# My_Smart_Home_Rev2.net
KiCad netlist of a schematic drawn in EAGLE
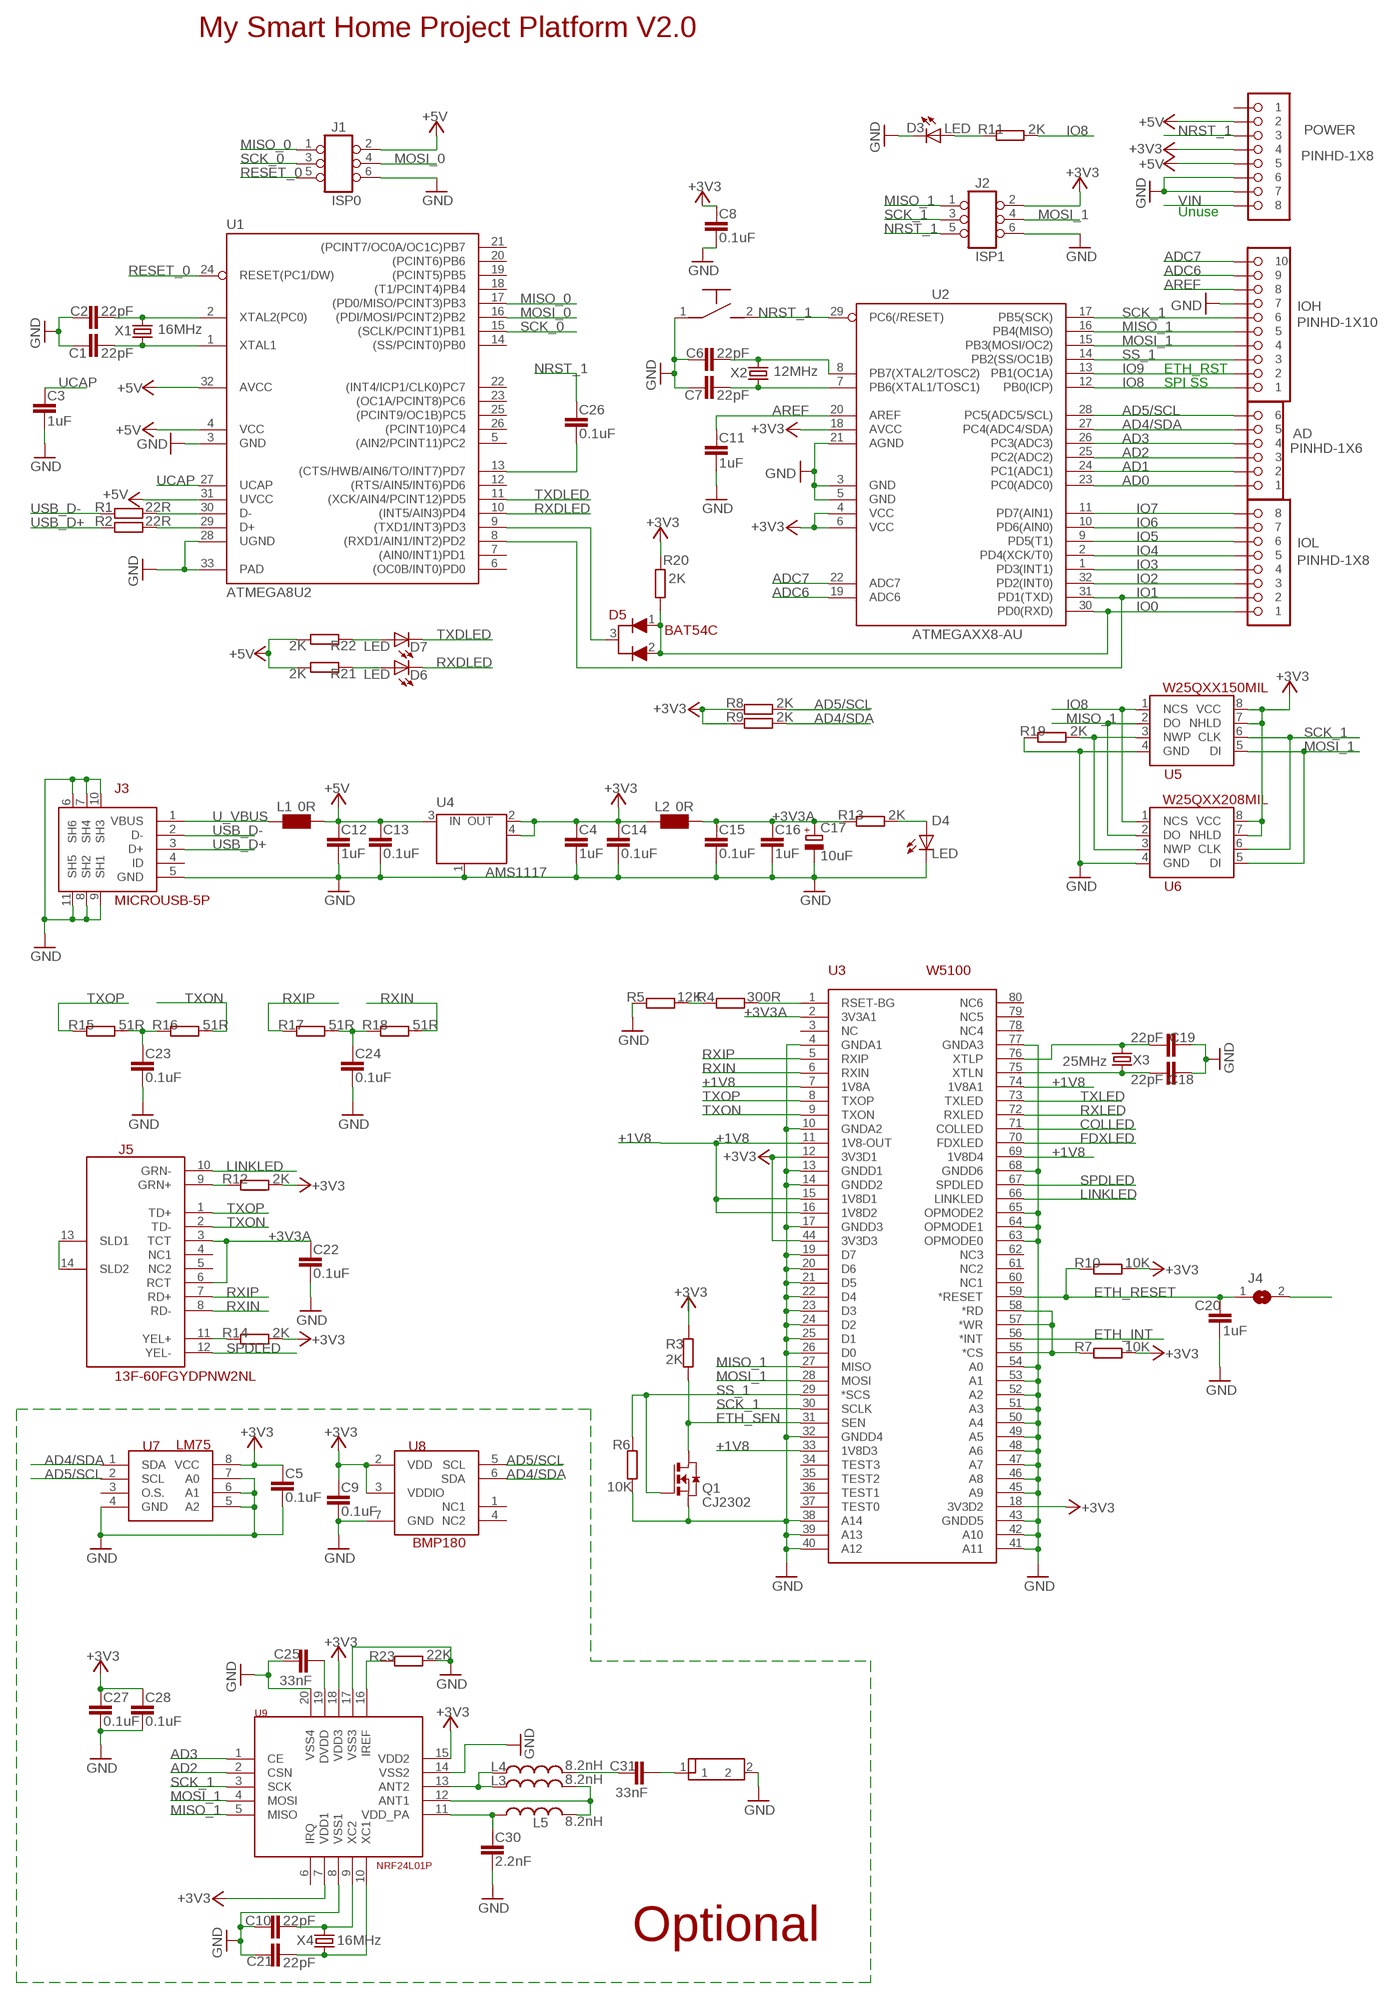
[diagram p0: schematic, sheet 1]

(export (version "E")
  (design (tool "Eeschema 10.0.6"))
  (components
    (comp (ref "AD")
      (value "PINHD-1X6")
      (footprint "eagle-import:1X06")
      (libsource (lib "eagle-import") (part "PINHD-1X6"))
    )
    (comp (ref "ANT1")
      (value "2.4G_ANT1")
      (footprint "eagle-import:2.4G_PCB_ANT")
      (libsource (lib "eagle-import") (part "2.4G_ANT1"))
    )
    (comp (ref "C1")
      (value "22pF")
      (footprint "eagle-import:C0603")
      (libsource (lib "eagle-import") (part "C-NP"))
    )
    (comp (ref "C2")
      (value "22pF")
      (footprint "eagle-import:C0603")
      (libsource (lib "eagle-import") (part "C-NP"))
    )
    (comp (ref "C3")
      (value "1uF")
      (footprint "eagle-import:C0603")
      (libsource (lib "eagle-import") (part "C-NP"))
    )
    (comp (ref "C4")
      (value "1uF")
      (footprint "eagle-import:C0603")
      (libsource (lib "eagle-import") (part "C-NP"))
    )
    (comp (ref "C5")
      (value "0.1uF")
      (footprint "eagle-import:C0603")
      (libsource (lib "eagle-import") (part "C-NP"))
    )
    (comp (ref "C6")
      (value "22pF")
      (footprint "eagle-import:C0603")
      (libsource (lib "eagle-import") (part "C-NP"))
    )
    (comp (ref "C7")
      (value "22pF")
      (footprint "eagle-import:C0603")
      (libsource (lib "eagle-import") (part "C-NP"))
    )
    (comp (ref "C8")
      (value "0.1uF")
      (footprint "eagle-import:C0603")
      (libsource (lib "eagle-import") (part "C-NP"))
    )
    (comp (ref "C9")
      (value "0.1uF")
      (footprint "eagle-import:C0603")
      (libsource (lib "eagle-import") (part "C-NP"))
    )
    (comp (ref "C10")
      (value "22pF")
      (footprint "eagle-import:C0603")
      (libsource (lib "eagle-import") (part "C-NP"))
    )
    (comp (ref "C11")
      (value "1uF")
      (footprint "eagle-import:C0603")
      (libsource (lib "eagle-import") (part "C-NP"))
    )
    (comp (ref "C12")
      (value "1uF")
      (footprint "eagle-import:C0603")
      (libsource (lib "eagle-import") (part "C-NP"))
    )
    (comp (ref "C13")
      (value "0.1uF")
      (footprint "eagle-import:C0603")
      (libsource (lib "eagle-import") (part "C-NP"))
    )
    (comp (ref "C14")
      (value "0.1uF")
      (footprint "eagle-import:C0603")
      (libsource (lib "eagle-import") (part "C-NP"))
    )
    (comp (ref "C15")
      (value "0.1uF")
      (footprint "eagle-import:C0603")
      (libsource (lib "eagle-import") (part "C-NP"))
    )
    (comp (ref "C16")
      (value "1uF")
      (footprint "eagle-import:C0603")
      (libsource (lib "eagle-import") (part "C-NP"))
    )
    (comp (ref "C17")
      (value "10uF")
      (footprint "eagle-import:C0805")
      (libsource (lib "eagle-import") (part "C-POL"))
    )
    (comp (ref "C18")
      (value "22pF")
      (footprint "eagle-import:C0603")
      (libsource (lib "eagle-import") (part "C-NP"))
    )
    (comp (ref "C19")
      (value "22pF")
      (footprint "eagle-import:C0603")
      (libsource (lib "eagle-import") (part "C-NP"))
    )
    (comp (ref "C20")
      (value "1uF")
      (footprint "eagle-import:C0603")
      (libsource (lib "eagle-import") (part "C-NP"))
    )
    (comp (ref "C21")
      (value "22pF")
      (footprint "eagle-import:C0603")
      (libsource (lib "eagle-import") (part "C-NP"))
    )
    (comp (ref "C22")
      (value "0.1uF")
      (footprint "eagle-import:C0603")
      (libsource (lib "eagle-import") (part "C-NP"))
    )
    (comp (ref "C23")
      (value "0.1uF")
      (footprint "eagle-import:C0603")
      (libsource (lib "eagle-import") (part "C-NP"))
    )
    (comp (ref "C24")
      (value "0.1uF")
      (footprint "eagle-import:C0603")
      (libsource (lib "eagle-import") (part "C-NP"))
    )
    (comp (ref "C25")
      (value "33nF")
      (footprint "eagle-import:C0603")
      (libsource (lib "eagle-import") (part "C-NP"))
    )
    (comp (ref "C26")
      (value "0.1uF")
      (footprint "eagle-import:C0603")
      (libsource (lib "eagle-import") (part "C-NP"))
    )
    (comp (ref "C27")
      (value "0.1uF")
      (footprint "eagle-import:C0603")
      (libsource (lib "eagle-import") (part "C-NP"))
    )
    (comp (ref "C28")
      (value "0.1uF")
      (footprint "eagle-import:C0603")
      (libsource (lib "eagle-import") (part "C-NP"))
    )
    (comp (ref "C30")
      (value "2.2nF")
      (footprint "eagle-import:C0603")
      (libsource (lib "eagle-import") (part "C-NP"))
    )
    (comp (ref "C31")
      (value "33nF")
      (footprint "eagle-import:C0603")
      (libsource (lib "eagle-import") (part "C-NP"))
    )
    (comp (ref "D3")
      (value "LED")
      (footprint "eagle-import:LED0805")
      (libsource (lib "eagle-import") (part "LED"))
    )
    (comp (ref "D4")
      (value "LED")
      (footprint "eagle-import:LED0805")
      (libsource (lib "eagle-import") (part "LED"))
    )
    (comp (ref "D5")
      (value "BAT54C")
      (footprint "eagle-import:SOT23")
      (libsource (lib "eagle-import") (part "BAT54C"))
    )
    (comp (ref "D6")
      (value "LED")
      (footprint "eagle-import:LED0805")
      (libsource (lib "eagle-import") (part "LED"))
    )
    (comp (ref "D7")
      (value "LED")
      (footprint "eagle-import:LED0805")
      (libsource (lib "eagle-import") (part "LED"))
    )
    (comp (ref "IOH")
      (value "PINHD-1X10")
      (footprint "eagle-import:1X10")
      (libsource (lib "eagle-import") (part "PINHD-1X10"))
    )
    (comp (ref "IOL")
      (value "PINHD-1X8")
      (footprint "eagle-import:1X08")
      (libsource (lib "eagle-import") (part "PINHD-1X8"))
    )
    (comp (ref "J1")
      (value "ISP0")
      (footprint "eagle-import:2X03")
      (libsource (lib "eagle-import") (part "PINHD-2X3"))
    )
    (comp (ref "J2")
      (value "ISP1")
      (footprint "eagle-import:2X03")
      (libsource (lib "eagle-import") (part "PINHD-2X3"))
    )
    (comp (ref "J3")
      (value "MICROUSB-5P")
      (footprint "eagle-import:MICROUSB-5P-SMD")
      (libsource (lib "eagle-import") (part "MICROUSB-5P"))
    )
    (comp (ref "J4")
      (value "JUMPER")
      (footprint "eagle-import:SOLDER_JUMPER")
      (libsource (lib "eagle-import") (part "JUMPER"))
    )
    (comp (ref "J5")
      (value "13F-60FGYDPNW2NL")
      (footprint "eagle-import:13F-60FGYDPNW2NL")
      (libsource (lib "eagle-import") (part "13F-60FGYDPNW2NL"))
    )
    (comp (ref "L1")
      (value "0R")
      (footprint "eagle-import:R0603")
      (libsource (lib "eagle-import") (part "L_M"))
    )
    (comp (ref "L2")
      (value "0R")
      (footprint "eagle-import:R0603")
      (libsource (lib "eagle-import") (part "L_M"))
    )
    (comp (ref "L3")
      (value "8.2nH")
      (footprint "eagle-import:R0603")
      (libsource (lib "eagle-import") (part "L"))
    )
    (comp (ref "L4")
      (value "8.2nH")
      (footprint "eagle-import:R0603")
      (libsource (lib "eagle-import") (part "L"))
    )
    (comp (ref "L5")
      (value "8.2nH")
      (footprint "eagle-import:R0603")
      (libsource (lib "eagle-import") (part "L"))
    )
    (comp (ref "POWER")
      (value "PINHD-1X8")
      (footprint "eagle-import:1X08")
      (libsource (lib "eagle-import") (part "PINHD-1X8"))
    )
    (comp (ref "Q1")
      (value "CJ2302")
      (footprint "eagle-import:SOT23")
      (libsource (lib "eagle-import") (part "NMOS-SOT23"))
    )
    (comp (ref "R1")
      (value "22R")
      (footprint "eagle-import:R0603")
      (libsource (lib "eagle-import") (part "RES"))
    )
    (comp (ref "R2")
      (value "22R")
      (footprint "eagle-import:R0603")
      (libsource (lib "eagle-import") (part "RES"))
    )
    (comp (ref "R3")
      (value "2K")
      (footprint "eagle-import:R0603")
      (libsource (lib "eagle-import") (part "RES"))
    )
    (comp (ref "R4")
      (value "300R")
      (footprint "eagle-import:R0603")
      (libsource (lib "eagle-import") (part "RES"))
    )
    (comp (ref "R5")
      (value "12K")
      (footprint "eagle-import:R0603")
      (libsource (lib "eagle-import") (part "RES"))
    )
    (comp (ref "R6")
      (value "10K")
      (footprint "eagle-import:R0603")
      (libsource (lib "eagle-import") (part "RES"))
    )
    (comp (ref "R7")
      (value "10K")
      (footprint "eagle-import:R0603")
      (libsource (lib "eagle-import") (part "RES"))
    )
    (comp (ref "R8")
      (value "2K")
      (footprint "eagle-import:R0603")
      (libsource (lib "eagle-import") (part "RES"))
    )
    (comp (ref "R9")
      (value "2K")
      (footprint "eagle-import:R0603")
      (libsource (lib "eagle-import") (part "RES"))
    )
    (comp (ref "R10")
      (value "10K")
      (footprint "eagle-import:R0603")
      (libsource (lib "eagle-import") (part "RES"))
    )
    (comp (ref "R11")
      (value "2K")
      (footprint "eagle-import:R0603")
      (libsource (lib "eagle-import") (part "RES"))
    )
    (comp (ref "R12")
      (value "2K")
      (footprint "eagle-import:R0603")
      (libsource (lib "eagle-import") (part "RES"))
    )
    (comp (ref "R13")
      (value "2K")
      (footprint "eagle-import:R0603")
      (libsource (lib "eagle-import") (part "RES"))
    )
    (comp (ref "R14")
      (value "2K")
      (footprint "eagle-import:R0603")
      (libsource (lib "eagle-import") (part "RES"))
    )
    (comp (ref "R15")
      (value "51R")
      (footprint "eagle-import:R0603")
      (libsource (lib "eagle-import") (part "RES"))
    )
    (comp (ref "R16")
      (value "51R")
      (footprint "eagle-import:R0603")
      (libsource (lib "eagle-import") (part "RES"))
    )
    (comp (ref "R17")
      (value "51R")
      (footprint "eagle-import:R0603")
      (libsource (lib "eagle-import") (part "RES"))
    )
    (comp (ref "R18")
      (value "51R")
      (footprint "eagle-import:R0603")
      (libsource (lib "eagle-import") (part "RES"))
    )
    (comp (ref "R19")
      (value "2K")
      (footprint "eagle-import:R0603")
      (libsource (lib "eagle-import") (part "RES"))
    )
    (comp (ref "R20")
      (value "2K")
      (footprint "eagle-import:R0603")
      (libsource (lib "eagle-import") (part "RES"))
    )
    (comp (ref "R21")
      (value "2K")
      (footprint "eagle-import:R0603")
      (libsource (lib "eagle-import") (part "RES"))
    )
    (comp (ref "R22")
      (value "2K")
      (footprint "eagle-import:R0603")
      (libsource (lib "eagle-import") (part "RES"))
    )
    (comp (ref "R23")
      (value "22K")
      (footprint "eagle-import:R0603")
      (libsource (lib "eagle-import") (part "RES"))
    )
    (comp (ref "SW2")
      (value "SW-2")
      (footprint "eagle-import:SW-2P-SMD")
      (libsource (lib "eagle-import") (part "SW-2"))
    )
    (comp (ref "U1")
      (value "ATMEGA8U2")
      (footprint "eagle-import:MLF32")
      (libsource (lib "eagle-import") (part "ATMEGA8U2"))
    )
    (comp (ref "U2")
      (value "ATMEGAXX8-AU")
      (footprint "eagle-import:TQFP32-08")
      (libsource (lib "eagle-import") (part "ATMEGAXX8-AU"))
    )
    (comp (ref "U3")
      (value "W5100")
      (footprint "eagle-import:SQFP-S-10X10-80")
      (libsource (lib "eagle-import") (part "W5100"))
    )
    (comp (ref "U4")
      (value "AMS1117")
      (footprint "eagle-import:SOT223")
      (libsource (lib "eagle-import") (part "AMS1117"))
    )
    (comp (ref "U5")
      (value "W25QXX150MIL")
      (footprint "eagle-import:8S1")
      (libsource (lib "eagle-import") (part "W25QXX150MIL"))
    )
    (comp (ref "U6")
      (value "W25QXX208MIL")
      (footprint "eagle-import:8S2")
      (libsource (lib "eagle-import") (part "W25QXX208MIL"))
    )
    (comp (ref "U7")
      (value "LM75")
      (footprint "eagle-import:8S1")
      (libsource (lib "eagle-import") (part "LM75"))
    )
    (comp (ref "U8")
      (value "BMP180")
      (footprint "eagle-import:LGA-7P")
      (libsource (lib "eagle-import") (part "BMP180"))
    )
    (comp (ref "U9")
      (value "NRF24L01P")
      (footprint "eagle-import:QFN20")
      (libsource (lib "eagle-import") (part "NRF24L01P"))
    )
    (comp (ref "X1")
      (value "16MHz")
      (footprint "eagle-import:HC49UP")
      (libsource (lib "eagle-import") (part "CRYSTAL"))
    )
    (comp (ref "X2")
      (value "12MHz")
      (footprint "eagle-import:HC49UP")
      (libsource (lib "eagle-import") (part "CRYSTAL"))
    )
    (comp (ref "X3")
      (value "25MHz")
      (footprint "eagle-import:HC49UP")
      (libsource (lib "eagle-import") (part "CRYSTAL"))
    )
    (comp (ref "X4")
      (value "16MHz")
      (footprint "eagle-import:HC49UP")
      (libsource (lib "eagle-import") (part "CRYSTAL"))
    )
  )
  (nets
    (net (code "1") (name "+3V3") (class "Default")
      (node (ref "C14") (pin "2") (pinfunction "2_2") (pintype "passive"))
      (node (ref "C27") (pin "2") (pinfunction "2_2") (pintype "passive"))
      (node (ref "C28") (pin "2") (pinfunction "2_2") (pintype "passive"))
      (node (ref "C4") (pin "2") (pinfunction "2_2") (pintype "passive"))
      (node (ref "C5") (pin "2") (pinfunction "2_2") (pintype "passive"))
      (node (ref "C8") (pin "2") (pinfunction "2_2") (pintype "passive"))
      (node (ref "C9") (pin "2") (pinfunction "2_2") (pintype "passive"))
      (node (ref "J2") (pin "2") (pinfunction "2_2") (pintype "passive"))
      (node (ref "L2") (pin "1") (pinfunction "1_1") (pintype "passive"))
      (node (ref "POWER") (pin "4") (pinfunction "4_4") (pintype "passive"))
      (node (ref "R10") (pin "2") (pinfunction "2_2") (pintype "passive"))
      (node (ref "R12") (pin "1") (pinfunction "1_1") (pintype "passive"))
      (node (ref "R14") (pin "1") (pinfunction "1_1") (pintype "passive"))
      (node (ref "R20") (pin "2") (pinfunction "2_2") (pintype "passive"))
      (node (ref "R3") (pin "2") (pinfunction "2_2") (pintype "passive"))
      (node (ref "R7") (pin "2") (pinfunction "2_2") (pintype "passive"))
      (node (ref "R8") (pin "2") (pinfunction "2_2") (pintype "passive"))
      (node (ref "R9") (pin "2") (pinfunction "2_2") (pintype "passive"))
      (node (ref "U2") (pin "18") (pinfunction "AVCC_18") (pintype "bidirectional"))
      (node (ref "U2") (pin "4") (pinfunction "VCC_4") (pintype "bidirectional"))
      (node (ref "U2") (pin "6") (pinfunction "VCC_6") (pintype "bidirectional"))
      (node (ref "U3") (pin "12") (pinfunction "3V3D1_12") (pintype "power_in"))
      (node (ref "U3") (pin "18") (pinfunction "3V3D2_18") (pintype "power_in"))
      (node (ref "U3") (pin "44") (pinfunction "3V3D3_44") (pintype "power_in"))
      (node (ref "U4") (pin "2") (pinfunction "OUT_2") (pintype "passive"))
      (node (ref "U4") (pin "4") (pinfunction "OUT_4") (pintype "passive"))
      (node (ref "U5") (pin "7") (pinfunction "NHLD_7") (pintype "bidirectional"))
      (node (ref "U5") (pin "8") (pinfunction "VCC_8") (pintype "bidirectional"))
      (node (ref "U6") (pin "7") (pinfunction "NHLD_7") (pintype "bidirectional"))
      (node (ref "U6") (pin "8") (pinfunction "VCC_8") (pintype "bidirectional"))
      (node (ref "U7") (pin "8") (pinfunction "VCC_8") (pintype "bidirectional"))
      (node (ref "U8") (pin "2") (pinfunction "VDD_2") (pintype "bidirectional"))
      (node (ref "U8") (pin "3") (pinfunction "VDDIO_3") (pintype "bidirectional"))
      (node (ref "U9") (pin "15") (pinfunction "VDD2_15") (pintype "bidirectional"))
      (node (ref "U9") (pin "18") (pinfunction "VDD3_18") (pintype "bidirectional"))
      (node (ref "U9") (pin "7") (pinfunction "VDD1_7") (pintype "bidirectional"))
    )
    (net (code "2") (name "+5V") (class "Default")
      (node (ref "C12") (pin "2") (pinfunction "2_2") (pintype "passive"))
      (node (ref "C13") (pin "2") (pinfunction "2_2") (pintype "passive"))
      (node (ref "J1") (pin "2") (pinfunction "2_2") (pintype "passive"))
      (node (ref "L1") (pin "2") (pinfunction "2_2") (pintype "passive"))
      (node (ref "POWER") (pin "2") (pinfunction "2_2") (pintype "passive"))
      (node (ref "POWER") (pin "5") (pinfunction "5_5") (pintype "passive"))
      (node (ref "R21") (pin "1") (pinfunction "1_1") (pintype "passive"))
      (node (ref "R22") (pin "1") (pinfunction "1_1") (pintype "passive"))
      (node (ref "U1") (pin "31") (pinfunction "UVCC_31") (pintype "power_in"))
      (node (ref "U1") (pin "32") (pinfunction "AVCC_32") (pintype "power_in"))
      (node (ref "U1") (pin "4") (pinfunction "VCC_4") (pintype "power_in"))
      (node (ref "U4") (pin "3") (pinfunction "IN_3") (pintype "input"))
    )
    (net (code "3") (name "/+1V8") (class "Default")
      (node (ref "U3") (pin "11") (pinfunction "1V8-OUT_11") (pintype "power_in"))
      (node (ref "U3") (pin "15") (pinfunction "1V8D1_15") (pintype "power_in"))
      (node (ref "U3") (pin "16") (pinfunction "1V8D2_16") (pintype "power_in"))
      (node (ref "U3") (pin "33") (pinfunction "1V8D3_33") (pintype "power_in"))
      (node (ref "U3") (pin "69") (pinfunction "1V8D4_69") (pintype "power_in"))
      (node (ref "U3") (pin "7") (pinfunction "1V8A_7") (pintype "power_in"))
      (node (ref "U3") (pin "74") (pinfunction "1V8A1_74") (pintype "power_in"))
    )
    (net (code "4") (name "/+3V3A") (class "Default")
      (node (ref "C15") (pin "2") (pinfunction "2_2") (pintype "passive"))
      (node (ref "C16") (pin "2") (pinfunction "2_2") (pintype "passive"))
      (node (ref "C17") (pin "1") (pinfunction "+_1") (pintype "passive"))
      (node (ref "C22") (pin "2") (pinfunction "2_2") (pintype "passive"))
      (node (ref "J5") (pin "3") (pinfunction "TCT_3") (pintype "bidirectional"))
      (node (ref "J5") (pin "6") (pinfunction "RCT_6") (pintype "bidirectional"))
      (node (ref "L2") (pin "2") (pinfunction "2_2") (pintype "passive"))
      (node (ref "R13") (pin "2") (pinfunction "2_2") (pintype "passive"))
      (node (ref "U3") (pin "2") (pinfunction "3V3A1_2") (pintype "power_in"))
    )
    (net (code "5") (name "/AD0") (class "Default")
      (node (ref "AD") (pin "1") (pinfunction "1_1") (pintype "passive"))
      (node (ref "U2") (pin "23") (pinfunction "PC0(ADC0)_23") (pintype "bidirectional"))
    )
    (net (code "6") (name "/AD1") (class "Default")
      (node (ref "AD") (pin "2") (pinfunction "2_2") (pintype "passive"))
      (node (ref "U2") (pin "24") (pinfunction "PC1(ADC1)_24") (pintype "bidirectional"))
    )
    (net (code "7") (name "/AD2") (class "Default")
      (node (ref "AD") (pin "3") (pinfunction "3_3") (pintype "passive"))
      (node (ref "U2") (pin "25") (pinfunction "PC2(ADC2)_25") (pintype "bidirectional"))
      (node (ref "U9") (pin "2") (pinfunction "CSN_2") (pintype "bidirectional"))
    )
    (net (code "8") (name "/AD3") (class "Default")
      (node (ref "AD") (pin "4") (pinfunction "4_4") (pintype "passive"))
      (node (ref "U2") (pin "26") (pinfunction "PC3(ADC3)_26") (pintype "bidirectional"))
      (node (ref "U9") (pin "1") (pinfunction "CE_1") (pintype "bidirectional"))
    )
    (net (code "9") (name "/AD4{slash}SDA") (class "Default")
      (node (ref "AD") (pin "5") (pinfunction "5_5") (pintype "passive"))
      (node (ref "R9") (pin "1") (pinfunction "1_1") (pintype "passive"))
      (node (ref "U2") (pin "27") (pinfunction "PC4(ADC4/SDA)_27") (pintype "bidirectional"))
      (node (ref "U7") (pin "1") (pinfunction "SDA_1") (pintype "bidirectional"))
      (node (ref "U8") (pin "6") (pinfunction "SDA_6") (pintype "bidirectional"))
    )
    (net (code "10") (name "/AD5{slash}SCL") (class "Default")
      (node (ref "AD") (pin "6") (pinfunction "6_6") (pintype "passive"))
      (node (ref "R8") (pin "1") (pinfunction "1_1") (pintype "passive"))
      (node (ref "U2") (pin "28") (pinfunction "PC5(ADC5/SCL)_28") (pintype "bidirectional"))
      (node (ref "U7") (pin "2") (pinfunction "SCL_2") (pintype "bidirectional"))
      (node (ref "U8") (pin "5") (pinfunction "SCL_5") (pintype "bidirectional"))
    )
    (net (code "11") (name "/ADC6") (class "Default")
      (node (ref "IOH") (pin "9") (pinfunction "9_9") (pintype "passive"))
      (node (ref "U2") (pin "19") (pinfunction "ADC6_19") (pintype "bidirectional"))
    )
    (net (code "12") (name "/ADC7") (class "Default")
      (node (ref "IOH") (pin "10") (pinfunction "10_10") (pintype "passive"))
      (node (ref "U2") (pin "22") (pinfunction "ADC7_22") (pintype "bidirectional"))
    )
    (net (code "13") (name "/AREF") (class "Default")
      (node (ref "C11") (pin "2") (pinfunction "2_2") (pintype "passive"))
      (node (ref "IOH") (pin "8") (pinfunction "8_8") (pintype "passive"))
      (node (ref "U2") (pin "20") (pinfunction "AREF_20") (pintype "bidirectional"))
    )
    (net (code "14") (name "/COLLED") (class "Default")
      (node (ref "U3") (pin "71") (pinfunction "COLLED_71") (pintype "output"))
    )
    (net (code "15") (name "/ETH_INT") (class "Default")
      (node (ref "U3") (pin "56") (pinfunction "*INT_56") (pintype "input"))
    )
    (net (code "16") (name "/ETH_RESET") (class "Default")
      (node (ref "C20") (pin "2") (pinfunction "2_2") (pintype "passive"))
      (node (ref "J4") (pin "1") (pinfunction "1_1") (pintype "passive"))
      (node (ref "R10") (pin "1") (pinfunction "1_1") (pintype "passive"))
      (node (ref "U3") (pin "59") (pinfunction "*RESET_59") (pintype "input"))
    )
    (net (code "17") (name "/ETH_SEN") (class "Default")
      (node (ref "Q1") (pin "3") (pinfunction "D_3") (pintype "passive"))
      (node (ref "R3") (pin "1") (pinfunction "1_1") (pintype "passive"))
      (node (ref "U3") (pin "31") (pinfunction "SEN_31") (pintype "input"))
    )
    (net (code "18") (name "/FDXLED") (class "Default")
      (node (ref "U3") (pin "70") (pinfunction "FDXLED_70") (pintype "output"))
    )
    (net (code "19") (name "/IO0") (class "Default")
      (node (ref "D5") (pin "1") (pinfunction "1_1") (pintype "bidirectional"))
      (node (ref "D5") (pin "2") (pinfunction "2_2") (pintype "bidirectional"))
      (node (ref "IOL") (pin "1") (pinfunction "1_1") (pintype "passive"))
      (node (ref "R20") (pin "1") (pinfunction "1_1") (pintype "passive"))
      (node (ref "U2") (pin "30") (pinfunction "PD0(RXD)_30") (pintype "bidirectional"))
    )
    (net (code "20") (name "/IO1") (class "Default")
      (node (ref "IOL") (pin "2") (pinfunction "2_2") (pintype "passive"))
      (node (ref "U1") (pin "8") (pinfunction "(RXD1/AIN1/INT2)PD2_8") (pintype "bidirectional"))
      (node (ref "U2") (pin "31") (pinfunction "PD1(TXD)_31") (pintype "bidirectional"))
    )
    (net (code "21") (name "/IO2") (class "Default")
      (node (ref "IOL") (pin "3") (pinfunction "3_3") (pintype "passive"))
      (node (ref "U2") (pin "32") (pinfunction "PD2(INT0)_32") (pintype "bidirectional"))
    )
    (net (code "22") (name "/IO3") (class "Default")
      (node (ref "IOL") (pin "4") (pinfunction "4_4") (pintype "passive"))
      (node (ref "U2") (pin "1") (pinfunction "PD3(INT1)_1") (pintype "bidirectional"))
    )
    (net (code "23") (name "/IO4") (class "Default")
      (node (ref "IOL") (pin "5") (pinfunction "5_5") (pintype "passive"))
      (node (ref "U2") (pin "2") (pinfunction "PD4(XCK/T0)_2") (pintype "bidirectional"))
    )
    (net (code "24") (name "/IO5") (class "Default")
      (node (ref "IOL") (pin "6") (pinfunction "6_6") (pintype "passive"))
      (node (ref "U2") (pin "9") (pinfunction "PD5(T1)_9") (pintype "bidirectional"))
    )
    (net (code "25") (name "/IO6") (class "Default")
      (node (ref "IOL") (pin "7") (pinfunction "7_7") (pintype "passive"))
      (node (ref "U2") (pin "10") (pinfunction "PD6(AIN0)_10") (pintype "bidirectional"))
    )
    (net (code "26") (name "/IO7") (class "Default")
      (node (ref "IOL") (pin "8") (pinfunction "8_8") (pintype "passive"))
      (node (ref "U2") (pin "11") (pinfunction "PD7(AIN1)_11") (pintype "bidirectional"))
    )
    (net (code "27") (name "/IO8") (class "Default")
      (node (ref "IOH") (pin "1") (pinfunction "1_1") (pintype "passive"))
      (node (ref "R11") (pin "1") (pinfunction "1_1") (pintype "passive"))
      (node (ref "U2") (pin "12") (pinfunction "PB0(ICP)_12") (pintype "bidirectional"))
      (node (ref "U5") (pin "1") (pinfunction "NCS_1") (pintype "bidirectional"))
      (node (ref "U6") (pin "1") (pinfunction "NCS_1") (pintype "bidirectional"))
    )
    (net (code "28") (name "/IO9") (class "Default")
      (node (ref "IOH") (pin "2") (pinfunction "2_2") (pintype "passive"))
      (node (ref "J4") (pin "2") (pinfunction "2_2") (pintype "passive"))
      (node (ref "U2") (pin "13") (pinfunction "PB1(OC1A)_13") (pintype "bidirectional"))
    )
    (net (code "29") (name "/LINKLED") (class "Default")
      (node (ref "J5") (pin "10") (pinfunction "GRN-_10") (pintype "bidirectional"))
      (node (ref "U3") (pin "66") (pinfunction "LINKLED_66") (pintype "output"))
    )
    (net (code "30") (name "/MISO_0") (class "Default")
      (node (ref "J1") (pin "1") (pinfunction "1_1") (pintype "passive"))
      (node (ref "U1") (pin "17") (pinfunction "(PD0/MISO/PCINT3)PB3_17") (pintype "bidirectional"))
    )
    (net (code "31") (name "/MISO_1") (class "Default")
      (node (ref "IOH") (pin "5") (pinfunction "5_5") (pintype "passive"))
      (node (ref "J2") (pin "1") (pinfunction "1_1") (pintype "passive"))
      (node (ref "U2") (pin "16") (pinfunction "PB4(MISO)_16") (pintype "bidirectional"))
      (node (ref "U3") (pin "27") (pinfunction "MISO_27") (pintype "input"))
      (node (ref "U5") (pin "2") (pinfunction "DO_2") (pintype "bidirectional"))
      (node (ref "U6") (pin "2") (pinfunction "DO_2") (pintype "bidirectional"))
      (node (ref "U9") (pin "5") (pinfunction "MISO_5") (pintype "bidirectional"))
    )
    (net (code "32") (name "/MOSI_0") (class "Default")
      (node (ref "J1") (pin "4") (pinfunction "4_4") (pintype "passive"))
      (node (ref "U1") (pin "16") (pinfunction "(PDI/MOSI/PCINT2)PB2_16") (pintype "bidirectional"))
    )
    (net (code "33") (name "/MOSI_1") (class "Default")
      (node (ref "IOH") (pin "4") (pinfunction "4_4") (pintype "passive"))
      (node (ref "J2") (pin "4") (pinfunction "4_4") (pintype "passive"))
      (node (ref "U2") (pin "15") (pinfunction "PB3(MOSI/OC2)_15") (pintype "bidirectional"))
      (node (ref "U3") (pin "28") (pinfunction "MOSI_28") (pintype "output"))
      (node (ref "U5") (pin "5") (pinfunction "DI_5") (pintype "bidirectional"))
      (node (ref "U6") (pin "5") (pinfunction "DI_5") (pintype "bidirectional"))
      (node (ref "U9") (pin "4") (pinfunction "MOSI_4") (pintype "bidirectional"))
    )
    (net (code "34") (name "/NRST_1") (class "Default")
      (node (ref "C26") (pin "2") (pinfunction "2_2") (pintype "passive"))
      (node (ref "J2") (pin "5") (pinfunction "5_5") (pintype "passive"))
      (node (ref "POWER") (pin "3") (pinfunction "3_3") (pintype "passive"))
      (node (ref "SW2") (pin "2") (pinfunction "P$2_2") (pintype "bidirectional"))
      (node (ref "U2") (pin "29") (pinfunction "PC6(/RESET)_29") (pintype "bidirectional"))
    )
    (net (code "35") (name "/RESET_0") (class "Default")
      (node (ref "J1") (pin "5") (pinfunction "5_5") (pintype "passive"))
      (node (ref "U1") (pin "24") (pinfunction "RESET(PC1/DW)_24") (pintype "input"))
    )
    (net (code "36") (name "/RXDLED") (class "Default")
      (node (ref "D6") (pin "C") (pinfunction "C_C") (pintype "passive"))
      (node (ref "U1") (pin "10") (pinfunction "(INT5/AIN3)PD4_10") (pintype "bidirectional"))
    )
    (net (code "37") (name "/RXIN") (class "Default")
      (node (ref "J5") (pin "8") (pinfunction "RD-_8") (pintype "bidirectional"))
      (node (ref "R18") (pin "1") (pinfunction "1_1") (pintype "passive"))
      (node (ref "U3") (pin "6") (pinfunction "RXIN_6") (pintype "input"))
    )
    (net (code "38") (name "/RXIP") (class "Default")
      (node (ref "J5") (pin "7") (pinfunction "RD+_7") (pintype "bidirectional"))
      (node (ref "R17") (pin "2") (pinfunction "2_2") (pintype "passive"))
      (node (ref "U3") (pin "5") (pinfunction "RXIP_5") (pintype "input"))
    )
    (net (code "39") (name "/RXLED") (class "Default")
      (node (ref "U3") (pin "72") (pinfunction "RXLED_72") (pintype "output"))
    )
    (net (code "40") (name "/SCK_0") (class "Default")
      (node (ref "J1") (pin "3") (pinfunction "3_3") (pintype "passive"))
      (node (ref "U1") (pin "15") (pinfunction "(SCLK/PCINT1)PB1_15") (pintype "bidirectional"))
    )
    (net (code "41") (name "/SCK_1") (class "Default")
      (node (ref "IOH") (pin "6") (pinfunction "6_6") (pintype "passive"))
      (node (ref "J2") (pin "3") (pinfunction "3_3") (pintype "passive"))
      (node (ref "U2") (pin "17") (pinfunction "PB5(SCK)_17") (pintype "bidirectional"))
      (node (ref "U3") (pin "30") (pinfunction "SCLK_30") (pintype "input"))
      (node (ref "U5") (pin "6") (pinfunction "CLK_6") (pintype "bidirectional"))
      (node (ref "U6") (pin "6") (pinfunction "CLK_6") (pintype "bidirectional"))
      (node (ref "U9") (pin "3") (pinfunction "SCK_3") (pintype "bidirectional"))
    )
    (net (code "42") (name "/SPDLED") (class "Default")
      (node (ref "J5") (pin "12") (pinfunction "YEL-_12") (pintype "bidirectional"))
      (node (ref "U3") (pin "67") (pinfunction "SPDLED_67") (pintype "output"))
    )
    (net (code "43") (name "/SS_1") (class "Default")
      (node (ref "IOH") (pin "3") (pinfunction "3_3") (pintype "passive"))
      (node (ref "Q1") (pin "1") (pinfunction "G_1") (pintype "passive"))
      (node (ref "R6") (pin "2") (pinfunction "2_2") (pintype "passive"))
      (node (ref "U2") (pin "14") (pinfunction "PB2(SS/OC1B)_14") (pintype "bidirectional"))
      (node (ref "U3") (pin "29") (pinfunction "*SCS_29") (pintype "input"))
    )
    (net (code "44") (name "/TXDLED") (class "Default")
      (node (ref "D7") (pin "C") (pinfunction "C_C") (pintype "passive"))
      (node (ref "U1") (pin "11") (pinfunction "(XCK/AIN4/PCINT12)PD5_11") (pintype "bidirectional"))
    )
    (net (code "45") (name "/TXLED") (class "Default")
      (node (ref "U3") (pin "73") (pinfunction "TXLED_73") (pintype "output"))
    )
    (net (code "46") (name "/TXON") (class "Default")
      (node (ref "J5") (pin "2") (pinfunction "TD-_2") (pintype "bidirectional"))
      (node (ref "R16") (pin "1") (pinfunction "1_1") (pintype "passive"))
      (node (ref "U3") (pin "9") (pinfunction "TXON_9") (pintype "output"))
    )
    (net (code "47") (name "/TXOP") (class "Default")
      (node (ref "J5") (pin "1") (pinfunction "TD+_1") (pintype "bidirectional"))
      (node (ref "R15") (pin "2") (pinfunction "2_2") (pintype "passive"))
      (node (ref "U3") (pin "8") (pinfunction "TXOP_8") (pintype "output"))
    )
    (net (code "48") (name "/UCAP") (class "Default")
      (node (ref "C3") (pin "2") (pinfunction "2_2") (pintype "passive"))
      (node (ref "U1") (pin "27") (pinfunction "UCAP_27") (pintype "passive"))
    )
    (net (code "49") (name "/USB_D+") (class "Default")
      (node (ref "J3") (pin "3") (pinfunction "D+_3") (pintype "bidirectional"))
      (node (ref "R2") (pin "1") (pinfunction "1_1") (pintype "passive"))
    )
    (net (code "50") (name "/USB_D-") (class "Default")
      (node (ref "J3") (pin "2") (pinfunction "D-_2") (pintype "bidirectional"))
      (node (ref "R1") (pin "1") (pinfunction "1_1") (pintype "passive"))
    )
    (net (code "51") (name "/U_VBUS") (class "Default")
      (node (ref "J3") (pin "1") (pinfunction "VBUS_1") (pintype "bidirectional"))
      (node (ref "L1") (pin "1") (pinfunction "1_1") (pintype "passive"))
    )
    (net (code "52") (name "/VIN") (class "Default")
      (node (ref "POWER") (pin "8") (pinfunction "8_8") (pintype "passive"))
    )
    (net (code "53") (name "GND") (class "Default")
      (node (ref "ANT1") (pin "2") (pinfunction "2_2") (pintype "bidirectional"))
      (node (ref "C1") (pin "1") (pinfunction "1_1") (pintype "passive"))
      (node (ref "C10") (pin "1") (pinfunction "1_1") (pintype "passive"))
      (node (ref "C11") (pin "1") (pinfunction "1_1") (pintype "passive"))
      (node (ref "C12") (pin "1") (pinfunction "1_1") (pintype "passive"))
      (node (ref "C13") (pin "1") (pinfunction "1_1") (pintype "passive"))
      (node (ref "C14") (pin "1") (pinfunction "1_1") (pintype "passive"))
      (node (ref "C15") (pin "1") (pinfunction "1_1") (pintype "passive"))
      (node (ref "C16") (pin "1") (pinfunction "1_1") (pintype "passive"))
      (node (ref "C17") (pin "2") (pinfunction "-_2") (pintype "passive"))
      (node (ref "C18") (pin "1") (pinfunction "1_1") (pintype "passive"))
      (node (ref "C19") (pin "1") (pinfunction "1_1") (pintype "passive"))
      (node (ref "C2") (pin "1") (pinfunction "1_1") (pintype "passive"))
      (node (ref "C20") (pin "1") (pinfunction "1_1") (pintype "passive"))
      (node (ref "C21") (pin "1") (pinfunction "1_1") (pintype "passive"))
      (node (ref "C22") (pin "1") (pinfunction "1_1") (pintype "passive"))
      (node (ref "C23") (pin "1") (pinfunction "1_1") (pintype "passive"))
      (node (ref "C24") (pin "1") (pinfunction "1_1") (pintype "passive"))
      (node (ref "C25") (pin "2") (pinfunction "2_2") (pintype "passive"))
      (node (ref "C27") (pin "1") (pinfunction "1_1") (pintype "passive"))
      (node (ref "C28") (pin "1") (pinfunction "1_1") (pintype "passive"))
      (node (ref "C3") (pin "1") (pinfunction "1_1") (pintype "passive"))
      (node (ref "C30") (pin "1") (pinfunction "1_1") (pintype "passive"))
      (node (ref "C4") (pin "1") (pinfunction "1_1") (pintype "passive"))
      (node (ref "C5") (pin "1") (pinfunction "1_1") (pintype "passive"))
      (node (ref "C6") (pin "1") (pinfunction "1_1") (pintype "passive"))
      (node (ref "C7") (pin "1") (pinfunction "1_1") (pintype "passive"))
      (node (ref "C8") (pin "1") (pinfunction "1_1") (pintype "passive"))
      (node (ref "C9") (pin "1") (pinfunction "1_1") (pintype "passive"))
      (node (ref "D3") (pin "C") (pinfunction "C_C") (pintype "passive"))
      (node (ref "D4") (pin "C") (pinfunction "C_C") (pintype "passive"))
      (node (ref "IOH") (pin "7") (pinfunction "7_7") (pintype "passive"))
      (node (ref "J1") (pin "6") (pinfunction "6_6") (pintype "passive"))
      (node (ref "J2") (pin "6") (pinfunction "6_6") (pintype "passive"))
      (node (ref "J3") (pin "10") (pinfunction "SH3_10") (pintype "bidirectional"))
      (node (ref "J3") (pin "11") (pinfunction "SH5_11") (pintype "bidirectional"))
      (node (ref "J3") (pin "5") (pinfunction "GND_5") (pintype "bidirectional"))
      (node (ref "J3") (pin "6") (pinfunction "SH6_6") (pintype "bidirectional"))
      (node (ref "J3") (pin "7") (pinfunction "SH4_7") (pintype "bidirectional"))
      (node (ref "J3") (pin "8") (pinfunction "SH2_8") (pintype "bidirectional"))
      (node (ref "J3") (pin "9") (pinfunction "SH1_9") (pintype "bidirectional"))
      (node (ref "POWER") (pin "6") (pinfunction "6_6") (pintype "passive"))
      (node (ref "POWER") (pin "7") (pinfunction "7_7") (pintype "passive"))
      (node (ref "Q1") (pin "2") (pinfunction "S_2") (pintype "passive"))
      (node (ref "R19") (pin "2") (pinfunction "2_2") (pintype "passive"))
      (node (ref "R23") (pin "1") (pinfunction "1_1") (pintype "passive"))
      (node (ref "R5") (pin "1") (pinfunction "1_1") (pintype "passive"))
      (node (ref "R6") (pin "1") (pinfunction "1_1") (pintype "passive"))
      (node (ref "SW2") (pin "1") (pinfunction "P$1_1") (pintype "bidirectional"))
      (node (ref "U1") (pin "28") (pinfunction "UGND_28") (pintype "power_in"))
      (node (ref "U1") (pin "3") (pinfunction "GND_3") (pintype "power_in"))
      (node (ref "U1") (pin "33") (pinfunction "PAD_33") (pintype "power_in"))
      (node (ref "U2") (pin "21") (pinfunction "AGND_21") (pintype "bidirectional"))
      (node (ref "U2") (pin "3") (pinfunction "GND_3") (pintype "bidirectional"))
      (node (ref "U2") (pin "5") (pinfunction "GND_5") (pintype "bidirectional"))
      (node (ref "U3") (pin "10") (pinfunction "GNDA2_10") (pintype "power_in"))
      (node (ref "U3") (pin "13") (pinfunction "GNDD1_13") (pintype "power_in"))
      (node (ref "U3") (pin "14") (pinfunction "GNDD2_14") (pintype "power_in"))
      (node (ref "U3") (pin "17") (pinfunction "GNDD3_17") (pintype "power_in"))
      (node (ref "U3") (pin "19") (pinfunction "D7_19") (pintype "input"))
      (node (ref "U3") (pin "20") (pinfunction "D6_20") (pintype "input"))
      (node (ref "U3") (pin "21") (pinfunction "D5_21") (pintype "input"))
      (node (ref "U3") (pin "22") (pinfunction "D4_22") (pintype "input"))
      (node (ref "U3") (pin "23") (pinfunction "D3_23") (pintype "input"))
      (node (ref "U3") (pin "24") (pinfunction "D2_24") (pintype "input"))
      (node (ref "U3") (pin "25") (pinfunction "D1_25") (pintype "input"))
      (node (ref "U3") (pin "26") (pinfunction "D0_26") (pintype "input"))
      (node (ref "U3") (pin "32") (pinfunction "GNDD4_32") (pintype "power_in"))
      (node (ref "U3") (pin "38") (pinfunction "A14_38") (pintype "input"))
      (node (ref "U3") (pin "39") (pinfunction "A13_39") (pintype "input"))
      (node (ref "U3") (pin "4") (pinfunction "GNDA1_4") (pintype "power_in"))
      (node (ref "U3") (pin "40") (pinfunction "A12_40") (pintype "input"))
      (node (ref "U3") (pin "41") (pinfunction "A11_41") (pintype "input"))
      (node (ref "U3") (pin "42") (pinfunction "A10_42") (pintype "input"))
      (node (ref "U3") (pin "43") (pinfunction "GNDD5_43") (pintype "power_in"))
      (node (ref "U3") (pin "45") (pinfunction "A9_45") (pintype "input"))
      (node (ref "U3") (pin "46") (pinfunction "A8_46") (pintype "input"))
      (node (ref "U3") (pin "47") (pinfunction "A7_47") (pintype "input"))
      (node (ref "U3") (pin "48") (pinfunction "A6_48") (pintype "input"))
      (node (ref "U3") (pin "49") (pinfunction "A5_49") (pintype "input"))
      (node (ref "U3") (pin "50") (pinfunction "A4_50") (pintype "input"))
      (node (ref "U3") (pin "51") (pinfunction "A3_51") (pintype "input"))
      (node (ref "U3") (pin "52") (pinfunction "A2_52") (pintype "input"))
      (node (ref "U3") (pin "53") (pinfunction "A1_53") (pintype "input"))
      (node (ref "U3") (pin "54") (pinfunction "A0_54") (pintype "input"))
      (node (ref "U3") (pin "63") (pinfunction "OPMODE0_63") (pintype "input"))
      (node (ref "U3") (pin "64") (pinfunction "OPMODE1_64") (pintype "input"))
      (node (ref "U3") (pin "65") (pinfunction "OPMODE2_65") (pintype "input"))
      (node (ref "U3") (pin "68") (pinfunction "GNDD6_68") (pintype "power_in"))
      (node (ref "U3") (pin "77") (pinfunction "GNDA3_77") (pintype "power_in"))
      (node (ref "U4") (pin "1") (pinfunction "GND/ADJ_1") (pintype "input"))
      (node (ref "U5") (pin "4") (pinfunction "GND_4") (pintype "bidirectional"))
      (node (ref "U6") (pin "4") (pinfunction "GND_4") (pintype "bidirectional"))
      (node (ref "U7") (pin "4") (pinfunction "GND_4") (pintype "bidirectional"))
      (node (ref "U7") (pin "5") (pinfunction "A2_5") (pintype "bidirectional"))
      (node (ref "U7") (pin "6") (pinfunction "A1_6") (pintype "bidirectional"))
      (node (ref "U7") (pin "7") (pinfunction "A0_7") (pintype "bidirectional"))
      (node (ref "U8") (pin "7") (pinfunction "GND_7") (pintype "bidirectional"))
      (node (ref "U9") (pin "14") (pinfunction "VSS2_14") (pintype "bidirectional"))
      (node (ref "U9") (pin "17") (pinfunction "VSS3_17") (pintype "bidirectional"))
      (node (ref "U9") (pin "20") (pinfunction "VSS4_20") (pintype "bidirectional"))
      (node (ref "U9") (pin "8") (pinfunction "VSS1_8") (pintype "bidirectional"))
    )
    (net (code "54") (name "Net-(ANT1-Pad1)") (class "Default")
      (node (ref "ANT1") (pin "1") (pinfunction "1_1") (pintype "bidirectional"))
      (node (ref "C31") (pin "1") (pinfunction "1_1") (pintype "passive"))
    )
    (net (code "55") (name "Net-(C23-Pad2)") (class "Default")
      (node (ref "C23") (pin "2") (pinfunction "2_2") (pintype "passive"))
      (node (ref "R15") (pin "1") (pinfunction "1_1") (pintype "passive"))
      (node (ref "R16") (pin "2") (pinfunction "2_2") (pintype "passive"))
    )
    (net (code "56") (name "Net-(C24-Pad2)") (class "Default")
      (node (ref "C24") (pin "2") (pinfunction "2_2") (pintype "passive"))
      (node (ref "R17") (pin "1") (pinfunction "1_1") (pintype "passive"))
      (node (ref "R18") (pin "2") (pinfunction "2_2") (pintype "passive"))
    )
    (net (code "57") (name "Net-(C31-Pad2)") (class "Default")
      (node (ref "C31") (pin "2") (pinfunction "2_2") (pintype "passive"))
      (node (ref "L4") (pin "2") (pinfunction "2_2") (pintype "passive"))
    )
    (net (code "58") (name "Net-(D3-PadA)") (class "Default")
      (node (ref "D3") (pin "A") (pinfunction "A_A") (pintype "passive"))
      (node (ref "R11") (pin "2") (pinfunction "2_2") (pintype "passive"))
    )
    (net (code "59") (name "Net-(D4-PadA)") (class "Default")
      (node (ref "D4") (pin "A") (pinfunction "A_A") (pintype "passive"))
      (node (ref "R13") (pin "1") (pinfunction "1_1") (pintype "passive"))
    )
    (net (code "60") (name "Net-(D6-PadA)") (class "Default")
      (node (ref "D6") (pin "A") (pinfunction "A_A") (pintype "passive"))
      (node (ref "R21") (pin "2") (pinfunction "2_2") (pintype "passive"))
    )
    (net (code "61") (name "Net-(D7-PadA)") (class "Default")
      (node (ref "D7") (pin "A") (pinfunction "A_A") (pintype "passive"))
      (node (ref "R22") (pin "2") (pinfunction "2_2") (pintype "passive"))
    )
    (net (code "62") (name "Net-(J5-GRN+)") (class "Default")
      (node (ref "J5") (pin "9") (pinfunction "GRN+_9") (pintype "bidirectional"))
      (node (ref "R12") (pin "2") (pinfunction "2_2") (pintype "passive"))
    )
    (net (code "63") (name "Net-(J5-SLD1)") (class "Default")
      (node (ref "J5") (pin "13") (pinfunction "SLD1_13") (pintype "bidirectional"))
      (node (ref "J5") (pin "14") (pinfunction "SLD2_14") (pintype "bidirectional"))
    )
    (net (code "64") (name "Net-(J5-YEL+)") (class "Default")
      (node (ref "J5") (pin "11") (pinfunction "YEL+_11") (pintype "bidirectional"))
      (node (ref "R14") (pin "2") (pinfunction "2_2") (pintype "passive"))
    )
    (net (code "65") (name "Net-(R4-Pad1)") (class "Default")
      (node (ref "R4") (pin "1") (pinfunction "1_1") (pintype "passive"))
      (node (ref "R5") (pin "2") (pinfunction "2_2") (pintype "passive"))
    )
    (net (code "66") (name "Net-(U1-(CTS{slash}HWB{slash}AIN6{slash}TO{slash}INT7)PD7)") (class "Default")
      (node (ref "C26") (pin "1") (pinfunction "1_1") (pintype "passive"))
      (node (ref "U1") (pin "13") (pinfunction "(CTS/HWB/AIN6/TO/INT7)PD7_13") (pintype "bidirectional"))
    )
    (net (code "67") (name "Net-(U1-(TXD1{slash}INT3)PD3)") (class "Default")
      (node (ref "D5") (pin "3") (pinfunction "3_3") (pintype "bidirectional"))
      (node (ref "U1") (pin "9") (pinfunction "(TXD1/INT3)PD3_9") (pintype "bidirectional"))
    )
    (net (code "68") (name "Net-(U1-D+)") (class "Default")
      (node (ref "R2") (pin "2") (pinfunction "2_2") (pintype "passive"))
      (node (ref "U1") (pin "29") (pinfunction "D+_29") (pintype "bidirectional"))
    )
    (net (code "69") (name "Net-(U1-D-)") (class "Default")
      (node (ref "R1") (pin "2") (pinfunction "2_2") (pintype "passive"))
      (node (ref "U1") (pin "30") (pinfunction "D-_30") (pintype "bidirectional"))
    )
    (net (code "70") (name "Net-(U1-XTAL1)") (class "Default")
      (node (ref "C1") (pin "2") (pinfunction "2_2") (pintype "passive"))
      (node (ref "U1") (pin "1") (pinfunction "XTAL1_1") (pintype "bidirectional"))
      (node (ref "X1") (pin "1") (pinfunction "1_1") (pintype "passive"))
    )
    (net (code "71") (name "Net-(U1-XTAL2(PC0))") (class "Default")
      (node (ref "C2") (pin "2") (pinfunction "2_2") (pintype "passive"))
      (node (ref "U1") (pin "2") (pinfunction "XTAL2(PC0)_2") (pintype "bidirectional"))
      (node (ref "X1") (pin "2") (pinfunction "2_2") (pintype "passive"))
    )
    (net (code "72") (name "Net-(U2-PB6(XTAL1{slash}TOSC1))") (class "Default")
      (node (ref "C7") (pin "2") (pinfunction "2_2") (pintype "passive"))
      (node (ref "U2") (pin "7") (pinfunction "PB6(XTAL1/TOSC1)_7") (pintype "bidirectional"))
      (node (ref "X2") (pin "1") (pinfunction "1_1") (pintype "passive"))
    )
    (net (code "73") (name "Net-(U2-PB7(XTAL2{slash}TOSC2))") (class "Default")
      (node (ref "C6") (pin "2") (pinfunction "2_2") (pintype "passive"))
      (node (ref "U2") (pin "8") (pinfunction "PB7(XTAL2/TOSC2)_8") (pintype "bidirectional"))
      (node (ref "X2") (pin "2") (pinfunction "2_2") (pintype "passive"))
    )
    (net (code "74") (name "Net-(U3-*CS)") (class "Default")
      (node (ref "R7") (pin "1") (pinfunction "1_1") (pintype "passive"))
      (node (ref "U3") (pin "55") (pinfunction "*CS_55") (pintype "input"))
      (node (ref "U3") (pin "57") (pinfunction "*WR_57") (pintype "input"))
      (node (ref "U3") (pin "58") (pinfunction "*RD_58") (pintype "input"))
    )
    (net (code "75") (name "Net-(U3-RSET-BG)") (class "Default")
      (node (ref "R4") (pin "2") (pinfunction "2_2") (pintype "passive"))
      (node (ref "U3") (pin "1") (pinfunction "RSET-BG_1") (pintype "input"))
    )
    (net (code "76") (name "Net-(U3-XTLN)") (class "Default")
      (node (ref "C18") (pin "2") (pinfunction "2_2") (pintype "passive"))
      (node (ref "U3") (pin "75") (pinfunction "XTLN_75") (pintype "output"))
      (node (ref "X3") (pin "2") (pinfunction "2_2") (pintype "passive"))
    )
    (net (code "77") (name "Net-(U3-XTLP)") (class "Default")
      (node (ref "C19") (pin "2") (pinfunction "2_2") (pintype "passive"))
      (node (ref "U3") (pin "76") (pinfunction "XTLP_76") (pintype "output"))
      (node (ref "X3") (pin "1") (pinfunction "1_1") (pintype "passive"))
    )
    (net (code "78") (name "Net-(U5-NWP)") (class "Default")
      (node (ref "R19") (pin "1") (pinfunction "1_1") (pintype "passive"))
      (node (ref "U5") (pin "3") (pinfunction "NWP_3") (pintype "bidirectional"))
      (node (ref "U6") (pin "3") (pinfunction "NWP_3") (pintype "bidirectional"))
    )
    (net (code "79") (name "Net-(U9-ANT1)") (class "Default")
      (node (ref "L3") (pin "2") (pinfunction "2_2") (pintype "passive"))
      (node (ref "L5") (pin "2") (pinfunction "2_2") (pintype "passive"))
      (node (ref "U9") (pin "12") (pinfunction "ANT1_12") (pintype "bidirectional"))
    )
    (net (code "80") (name "Net-(U9-ANT2)") (class "Default")
      (node (ref "L3") (pin "1") (pinfunction "1_1") (pintype "passive"))
      (node (ref "L4") (pin "1") (pinfunction "1_1") (pintype "passive"))
      (node (ref "U9") (pin "13") (pinfunction "ANT2_13") (pintype "bidirectional"))
    )
    (net (code "81") (name "Net-(U9-DVDD)") (class "Default")
      (node (ref "C25") (pin "1") (pinfunction "1_1") (pintype "passive"))
      (node (ref "U9") (pin "19") (pinfunction "DVDD_19") (pintype "bidirectional"))
    )
    (net (code "82") (name "Net-(U9-IREF)") (class "Default")
      (node (ref "R23") (pin "2") (pinfunction "2_2") (pintype "passive"))
      (node (ref "U9") (pin "16") (pinfunction "IREF_16") (pintype "bidirectional"))
    )
    (net (code "83") (name "Net-(U9-VDD_PA)") (class "Default")
      (node (ref "C30") (pin "2") (pinfunction "2_2") (pintype "passive"))
      (node (ref "L5") (pin "1") (pinfunction "1_1") (pintype "passive"))
      (node (ref "U9") (pin "11") (pinfunction "VDD_PA_11") (pintype "bidirectional"))
    )
    (net (code "84") (name "Net-(U9-XC1)") (class "Default")
      (node (ref "C21") (pin "2") (pinfunction "2_2") (pintype "passive"))
      (node (ref "U9") (pin "10") (pinfunction "XC1_10") (pintype "bidirectional"))
      (node (ref "X4") (pin "1") (pinfunction "1_1") (pintype "passive"))
    )
    (net (code "85") (name "Net-(U9-XC2)") (class "Default")
      (node (ref "C10") (pin "2") (pinfunction "2_2") (pintype "passive"))
      (node (ref "U9") (pin "9") (pinfunction "XC2_9") (pintype "bidirectional"))
      (node (ref "X4") (pin "2") (pinfunction "2_2") (pintype "passive"))
    )
    (net (code "86") (name "unconnected-(J3-ID-Pad4)") (class "Default")
      (node (ref "J3") (pin "4") (pinfunction "ID_4") (pintype "bidirectional"))
    )
    (net (code "87") (name "unconnected-(J5-NC1-Pad4)") (class "Default")
      (node (ref "J5") (pin "4") (pinfunction "NC1_4") (pintype "bidirectional"))
    )
    (net (code "88") (name "unconnected-(J5-NC2-Pad5)") (class "Default")
      (node (ref "J5") (pin "5") (pinfunction "NC2_5") (pintype "bidirectional"))
    )
    (net (code "89") (name "unconnected-(POWER-Pad1)") (class "Default")
      (node (ref "POWER") (pin "1") (pinfunction "1_1") (pintype "passive"))
    )
    (net (code "90") (name "unconnected-(U1-(AIN0{slash}INT1)PD1-Pad7)") (class "Default")
      (node (ref "U1") (pin "7") (pinfunction "(AIN0/INT1)PD1_7") (pintype "bidirectional"))
    )
    (net (code "91") (name "unconnected-(U1-(AIN2{slash}PCINT11)PC2-Pad5)") (class "Default")
      (node (ref "U1") (pin "5") (pinfunction "(AIN2/PCINT11)PC2_5") (pintype "bidirectional"))
    )
    (net (code "92") (name "unconnected-(U1-(INT4{slash}ICP1{slash}CLK0)PC7-Pad22)") (class "Default")
      (node (ref "U1") (pin "22") (pinfunction "(INT4/ICP1/CLK0)PC7_22") (pintype "bidirectional"))
    )
    (net (code "93") (name "unconnected-(U1-(OC0B{slash}INT0)PD0-Pad6)") (class "Default")
      (node (ref "U1") (pin "6") (pinfunction "(OC0B/INT0)PD0_6") (pintype "bidirectional"))
    )
    (net (code "94") (name "unconnected-(U1-(OC1A{slash}PCINT8)PC6-Pad23)") (class "Default")
      (node (ref "U1") (pin "23") (pinfunction "(OC1A/PCINT8)PC6_23") (pintype "bidirectional"))
    )
    (net (code "95") (name "unconnected-(U1-(PCINT5)PB5-Pad19)") (class "Default")
      (node (ref "U1") (pin "19") (pinfunction "(PCINT5)PB5_19") (pintype "bidirectional"))
    )
    (net (code "96") (name "unconnected-(U1-(PCINT6)PB6-Pad20)") (class "Default")
      (node (ref "U1") (pin "20") (pinfunction "(PCINT6)PB6_20") (pintype "bidirectional"))
    )
    (net (code "97") (name "unconnected-(U1-(PCINT7{slash}OC0A{slash}OC1C)PB7-Pad21)") (class "Default")
      (node (ref "U1") (pin "21") (pinfunction "(PCINT7/OC0A/OC1C)PB7_21") (pintype "bidirectional"))
    )
    (net (code "98") (name "unconnected-(U1-(PCINT9{slash}OC1B)PC5-Pad25)") (class "Default")
      (node (ref "U1") (pin "25") (pinfunction "(PCINT9/OC1B)PC5_25") (pintype "bidirectional"))
    )
    (net (code "99") (name "unconnected-(U1-(PCINT10)PC4-Pad26)") (class "Default")
      (node (ref "U1") (pin "26") (pinfunction "(PCINT10)PC4_26") (pintype "bidirectional"))
    )
    (net (code "100") (name "unconnected-(U1-(RTS{slash}AIN5{slash}INT6)PD6-Pad12)") (class "Default")
      (node (ref "U1") (pin "12") (pinfunction "(RTS/AIN5/INT6)PD6_12") (pintype "bidirectional"))
    )
    (net (code "101") (name "unconnected-(U1-(SS{slash}PCINT0)PB0-Pad14)") (class "Default")
      (node (ref "U1") (pin "14") (pinfunction "(SS/PCINT0)PB0_14") (pintype "bidirectional"))
    )
    (net (code "102") (name "unconnected-(U1-(T1{slash}PCINT4)PB4-Pad18)") (class "Default")
      (node (ref "U1") (pin "18") (pinfunction "(T1/PCINT4)PB4_18") (pintype "bidirectional"))
    )
    (net (code "103") (name "unconnected-(U3-NC-Pad3)") (class "Default")
      (node (ref "U3") (pin "3") (pinfunction "NC_3") (pintype "no_connect"))
    )
    (net (code "104") (name "unconnected-(U3-NC1-Pad60)") (class "Default")
      (node (ref "U3") (pin "60") (pinfunction "NC1_60") (pintype "no_connect"))
    )
    (net (code "105") (name "unconnected-(U3-NC2-Pad61)") (class "Default")
      (node (ref "U3") (pin "61") (pinfunction "NC2_61") (pintype "no_connect"))
    )
    (net (code "106") (name "unconnected-(U3-NC3-Pad62)") (class "Default")
      (node (ref "U3") (pin "62") (pinfunction "NC3_62") (pintype "no_connect"))
    )
    (net (code "107") (name "unconnected-(U3-NC4-Pad78)") (class "Default")
      (node (ref "U3") (pin "78") (pinfunction "NC4_78") (pintype "no_connect"))
    )
    (net (code "108") (name "unconnected-(U3-NC5-Pad79)") (class "Default")
      (node (ref "U3") (pin "79") (pinfunction "NC5_79") (pintype "no_connect"))
    )
    (net (code "109") (name "unconnected-(U3-NC6-Pad80)") (class "Default")
      (node (ref "U3") (pin "80") (pinfunction "NC6_80") (pintype "no_connect"))
    )
    (net (code "110") (name "unconnected-(U3-TEST0-Pad37)") (class "Default")
      (node (ref "U3") (pin "37") (pinfunction "TEST0_37") (pintype "input"))
    )
    (net (code "111") (name "unconnected-(U3-TEST1-Pad36)") (class "Default")
      (node (ref "U3") (pin "36") (pinfunction "TEST1_36") (pintype "input"))
    )
    (net (code "112") (name "unconnected-(U3-TEST2-Pad35)") (class "Default")
      (node (ref "U3") (pin "35") (pinfunction "TEST2_35") (pintype "input"))
    )
    (net (code "113") (name "unconnected-(U3-TEST3-Pad34)") (class "Default")
      (node (ref "U3") (pin "34") (pinfunction "TEST3_34") (pintype "input"))
    )
    (net (code "114") (name "unconnected-(U7-O.S.-Pad3)") (class "Default")
      (node (ref "U7") (pin "3") (pinfunction "O.S._3") (pintype "bidirectional"))
    )
    (net (code "115") (name "unconnected-(U8-NC1-Pad1)") (class "Default")
      (node (ref "U8") (pin "1") (pinfunction "NC1_1") (pintype "bidirectional"))
    )
    (net (code "116") (name "unconnected-(U8-NC2-Pad4)") (class "Default")
      (node (ref "U8") (pin "4") (pinfunction "NC2_4") (pintype "bidirectional"))
    )
    (net (code "117") (name "unconnected-(U9-IRQ-Pad6)") (class "Default")
      (node (ref "U9") (pin "6") (pinfunction "IRQ_6") (pintype "bidirectional"))
    )
  )
)
